# Sheet3.net
KiCad netlist of a schematic drawn in Altium Designer
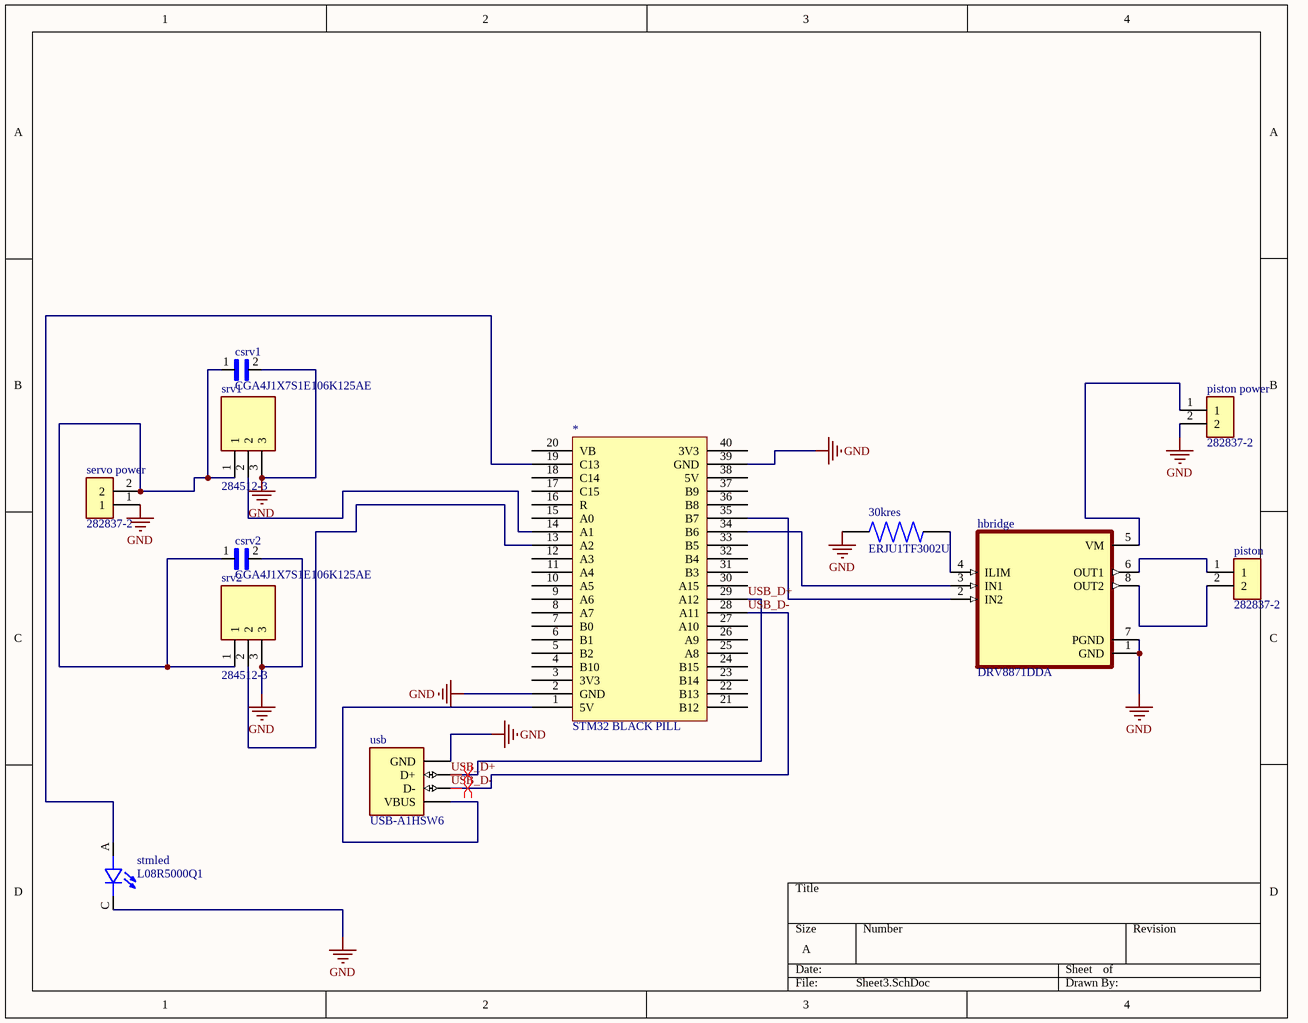
[diagram p0: Sheet3.SchDoc]

(export (version "E")
  (design (tool "Eeschema 10.0.6"))
  (components
    (comp (ref "*")
      (value "STM32 BLACK PILL")
      (footprint "STM 32 Black Pill")
      (fields (field (name "SOURCE") "STM 32 Balck Pill.SchLib"))
      (libsource (lib "Es John") (part "STM32 BLACK PILL"))
    )
    (comp (ref "30kres")
      (value "ERJU1TF3002U")
      (footprint "RES_ERJU1TF3002U")
      (libsource (lib "ERJU1TF3002U") (part "ERJU1TF3002U"))
    )
    (comp (ref "csrv1")
      (value "CGA4J1X7S1E106K125AE")
      (footprint "CAPC2012X150N")
      (description "10 ÂµF Â±10% 25V Ceramic Capacitor X7S 0805 (2012 Metric)")
      (fields (field (name "MF") "TDK") (field (name "DIGI-KEY_PART_NUMBER") "445-181411-2-ND"))
      (libsource (lib "CGA4J1X7S1E106K125AE") (part "CGA4J1X7S1E106K125AE"))
    )
    (comp (ref "csrv2")
      (value "CGA4J1X7S1E106K125AE")
      (footprint "CAPC2012X150N")
      (description "10 ÂµF Â±10% 25V Ceramic Capacitor X7S 0805 (2012 Metric)")
      (fields (field (name "MF") "TDK") (field (name "DIGI-KEY_PART_NUMBER") "445-181411-2-ND"))
      (libsource (lib "CGA4J1X7S1E106K125AE") (part "CGA4J1X7S1E106K125AE"))
    )
    (comp (ref "hbridge")
      (value "DRV8871DDA")
      (footprint "VREG_LM5017MR/NOPB")
      (description "50-V, 3.6-A H-bridge motor driver with integrated current sensing")
      (fields (field (name "MF") "Texas Instruments"))
      (libsource (lib "DRV8871DDA") (part "DRV8871DDA"))
    )
    (comp (ref "piston")
      (value "282837-2")
      (footprint "TE_282837-2")
      (fields (field (name "MF") "TE Connectivity"))
      (libsource (lib "282837-2 (1)") (part "282837-2"))
    )
    (comp (ref "piston power")
      (value "282837-2")
      (footprint "TE_282837-2")
      (fields (field (name "MF") "TE Connectivity"))
      (libsource (lib "282837-2 (1)") (part "282837-2"))
    )
    (comp (ref "servo power")
      (value "282837-2")
      (footprint "TE_282837-2")
      (fields (field (name "MF") "TE Connectivity"))
      (libsource (lib "") (part "282837-2_1"))
    )
    (comp (ref "srv1")
      (value "284512-3")
      (footprint "TE_284512-3")
      (fields (field (name "MF") "TE Connectivity"))
      (libsource (lib "284512-3") (part "284512-3"))
    )
    (comp (ref "srv2")
      (value "284512-3")
      (footprint "TE_284512-3")
      (fields (field (name "MF") "TE Connectivity"))
      (libsource (lib "284512-3") (part "284512-3"))
    )
    (comp (ref "stmled")
      (value "L08R5000Q1")
      (footprint "LEDRD254W57D500H1070")
      (fields (field (name "MF") "LED Technology"))
      (libsource (lib "L08R5000Q1") (part "L08R5000Q1"))
    )
    (comp (ref "usb")
      (value "USB-A1HSW6")
      (footprint "OST_USB-A1HSW6")
      (fields (field (name "MF") "{'manufacturer': u'On Shore Technology Inc.'}"))
      (libsource (lib "USB-A1HSW6") (part "USB-A1HSW6"))
    )
  )
  (nets
    (net (code "1") (name "/USB_D+") (class "Default")
      (node (ref "*") (pin "29") (pinfunction "A12_29") (pintype "passive"))
      (node (ref "usb") (pin "3") (pinfunction "D+_3") (pintype "bidirectional"))
    )
    (net (code "2") (name "/USB_D-") (class "Default")
      (node (ref "*") (pin "28") (pinfunction "A11_28") (pintype "passive"))
      (node (ref "usb") (pin "2") (pinfunction "D-_2") (pintype "bidirectional"))
    )
    (net (code "3") (name "GND") (class "Default")
      (node (ref "*") (pin "2") (pinfunction "GND_2") (pintype "passive"))
      (node (ref "*") (pin "39") (pinfunction "GND_39") (pintype "passive"))
      (node (ref "30kres") (pin "1") (pinfunction "1_1") (pintype "passive"))
      (node (ref "csrv1") (pin "2") (pinfunction "2_2") (pintype "passive"))
      (node (ref "csrv2") (pin "2") (pinfunction "2_2") (pintype "passive"))
      (node (ref "hbridge") (pin "1") (pinfunction "GND_1") (pintype "power_in"))
      (node (ref "hbridge") (pin "7") (pinfunction "PGND_7") (pintype "power_in"))
      (node (ref "piston power") (pin "2") (pinfunction "2_2") (pintype "passive"))
      (node (ref "servo power") (pin "1") (pinfunction "1_1") (pintype "passive"))
      (node (ref "srv1") (pin "3") (pinfunction "3_3") (pintype "passive"))
      (node (ref "srv2") (pin "3") (pinfunction "3_3") (pintype "passive"))
      (node (ref "stmled") (pin "C") (pinfunction "C_C") (pintype "passive"))
      (node (ref "usb") (pin "4") (pinfunction "GND_4") (pintype "power_in"))
    )
    (net (code "4") (name "Net-(*-A1)") (class "Default")
      (node (ref "*") (pin "14") (pinfunction "A1_14") (pintype "passive"))
      (node (ref "srv1") (pin "2") (pinfunction "2_2") (pintype "passive"))
    )
    (net (code "5") (name "Net-(*-A2)") (class "Default")
      (node (ref "*") (pin "13") (pinfunction "A2_13") (pintype "passive"))
      (node (ref "srv2") (pin "2") (pinfunction "2_2") (pintype "passive"))
    )
    (net (code "6") (name "Net-(*-B6)") (class "Default")
      (node (ref "*") (pin "34") (pinfunction "B6_34") (pintype "passive"))
      (node (ref "hbridge") (pin "3") (pinfunction "IN1_3") (pintype "input"))
    )
    (net (code "7") (name "Net-(*-B7)") (class "Default")
      (node (ref "*") (pin "35") (pinfunction "B7_35") (pintype "passive"))
      (node (ref "hbridge") (pin "2") (pinfunction "IN2_2") (pintype "input"))
    )
    (net (code "8") (name "Net-(*-C13)") (class "Default")
      (node (ref "*") (pin "19") (pinfunction "C13_19") (pintype "passive"))
      (node (ref "stmled") (pin "A") (pinfunction "A_A") (pintype "passive"))
    )
    (net (code "9") (name "Net-(csrv1-Pad1)") (class "Default")
      (node (ref "csrv1") (pin "1") (pinfunction "1_1") (pintype "passive"))
      (node (ref "csrv2") (pin "1") (pinfunction "1_1") (pintype "passive"))
      (node (ref "servo power") (pin "2") (pinfunction "2_2") (pintype "passive"))
      (node (ref "srv1") (pin "1") (pinfunction "1_1") (pintype "passive"))
      (node (ref "srv2") (pin "1") (pinfunction "1_1") (pintype "passive"))
    )
    (net (code "10") (name "Net-(hbridge-ILIM)") (class "Default")
      (node (ref "30kres") (pin "2") (pinfunction "2_2") (pintype "passive"))
      (node (ref "hbridge") (pin "4") (pinfunction "ILIM_4") (pintype "input"))
    )
    (net (code "11") (name "Net-(hbridge-OUT1)") (class "Default")
      (node (ref "hbridge") (pin "6") (pinfunction "OUT1_6") (pintype "output"))
      (node (ref "piston") (pin "1") (pinfunction "1_1") (pintype "passive"))
    )
    (net (code "12") (name "Net-(hbridge-OUT2)") (class "Default")
      (node (ref "hbridge") (pin "8") (pinfunction "OUT2_8") (pintype "output"))
      (node (ref "piston") (pin "2") (pinfunction "2_2") (pintype "passive"))
    )
    (net (code "13") (name "Net-(hbridge-VM)") (class "Default")
      (node (ref "hbridge") (pin "5") (pinfunction "VM_5") (pintype "power_in"))
      (node (ref "piston power") (pin "1") (pinfunction "1_1") (pintype "passive"))
    )
    (net (code "14") (name "Net-(usb-VBUS)") (class "Default")
      (node (ref "*") (pin "1") (pinfunction "5V_1") (pintype "passive"))
      (node (ref "usb") (pin "1") (pinfunction "VBUS_1") (pintype "power_in"))
    )
    (net (code "15") (name "unconnected-(*-3V3-Pad3)") (class "Default")
      (node (ref "*") (pin "3") (pinfunction "3V3_3") (pintype "passive"))
    )
    (net (code "16") (name "unconnected-(*-3V3-Pad40)") (class "Default")
      (node (ref "*") (pin "40") (pinfunction "3V3_40") (pintype "passive"))
    )
    (net (code "17") (name "unconnected-(*-5V-Pad38)") (class "Default")
      (node (ref "*") (pin "38") (pinfunction "5V_38") (pintype "passive"))
    )
    (net (code "18") (name "unconnected-(*-A0-Pad15)") (class "Default")
      (node (ref "*") (pin "15") (pinfunction "A0_15") (pintype "passive"))
    )
    (net (code "19") (name "unconnected-(*-A3-Pad12)") (class "Default")
      (node (ref "*") (pin "12") (pinfunction "A3_12") (pintype "passive"))
    )
    (net (code "20") (name "unconnected-(*-A4-Pad11)") (class "Default")
      (node (ref "*") (pin "11") (pinfunction "A4_11") (pintype "passive"))
    )
    (net (code "21") (name "unconnected-(*-A5-Pad10)") (class "Default")
      (node (ref "*") (pin "10") (pinfunction "A5_10") (pintype "passive"))
    )
    (net (code "22") (name "unconnected-(*-A6-Pad9)") (class "Default")
      (node (ref "*") (pin "9") (pinfunction "A6_9") (pintype "passive"))
    )
    (net (code "23") (name "unconnected-(*-A7-Pad8)") (class "Default")
      (node (ref "*") (pin "8") (pinfunction "A7_8") (pintype "passive"))
    )
    (net (code "24") (name "unconnected-(*-A8-Pad25)") (class "Default")
      (node (ref "*") (pin "25") (pinfunction "A8_25") (pintype "passive"))
    )
    (net (code "25") (name "unconnected-(*-A9-Pad26)") (class "Default")
      (node (ref "*") (pin "26") (pinfunction "A9_26") (pintype "passive"))
    )
    (net (code "26") (name "unconnected-(*-A10-Pad27)") (class "Default")
      (node (ref "*") (pin "27") (pinfunction "A10_27") (pintype "passive"))
    )
    (net (code "27") (name "unconnected-(*-A15-Pad30)") (class "Default")
      (node (ref "*") (pin "30") (pinfunction "A15_30") (pintype "passive"))
    )
    (net (code "28") (name "unconnected-(*-B0-Pad7)") (class "Default")
      (node (ref "*") (pin "7") (pinfunction "B0_7") (pintype "passive"))
    )
    (net (code "29") (name "unconnected-(*-B1-Pad6)") (class "Default")
      (node (ref "*") (pin "6") (pinfunction "B1_6") (pintype "passive"))
    )
    (net (code "30") (name "unconnected-(*-B2-Pad5)") (class "Default")
      (node (ref "*") (pin "5") (pinfunction "B2_5") (pintype "passive"))
    )
    (net (code "31") (name "unconnected-(*-B3-Pad31)") (class "Default")
      (node (ref "*") (pin "31") (pinfunction "B3_31") (pintype "passive"))
    )
    (net (code "32") (name "unconnected-(*-B4-Pad32)") (class "Default")
      (node (ref "*") (pin "32") (pinfunction "B4_32") (pintype "passive"))
    )
    (net (code "33") (name "unconnected-(*-B5-Pad33)") (class "Default")
      (node (ref "*") (pin "33") (pinfunction "B5_33") (pintype "passive"))
    )
    (net (code "34") (name "unconnected-(*-B8-Pad36)") (class "Default")
      (node (ref "*") (pin "36") (pinfunction "B8_36") (pintype "passive"))
    )
    (net (code "35") (name "unconnected-(*-B9-Pad37)") (class "Default")
      (node (ref "*") (pin "37") (pinfunction "B9_37") (pintype "passive"))
    )
    (net (code "36") (name "unconnected-(*-B10-Pad4)") (class "Default")
      (node (ref "*") (pin "4") (pinfunction "B10_4") (pintype "passive"))
    )
    (net (code "37") (name "unconnected-(*-B12-Pad21)") (class "Default")
      (node (ref "*") (pin "21") (pinfunction "B12_21") (pintype "passive"))
    )
    (net (code "38") (name "unconnected-(*-B13-Pad22)") (class "Default")
      (node (ref "*") (pin "22") (pinfunction "B13_22") (pintype "passive"))
    )
    (net (code "39") (name "unconnected-(*-B14-Pad23)") (class "Default")
      (node (ref "*") (pin "23") (pinfunction "B14_23") (pintype "passive"))
    )
    (net (code "40") (name "unconnected-(*-B15-Pad24)") (class "Default")
      (node (ref "*") (pin "24") (pinfunction "B15_24") (pintype "passive"))
    )
    (net (code "41") (name "unconnected-(*-C14-Pad18)") (class "Default")
      (node (ref "*") (pin "18") (pinfunction "C14_18") (pintype "passive"))
    )
    (net (code "42") (name "unconnected-(*-C15-Pad17)") (class "Default")
      (node (ref "*") (pin "17") (pinfunction "C15_17") (pintype "passive"))
    )
    (net (code "43") (name "unconnected-(*-R-Pad16)") (class "Default")
      (node (ref "*") (pin "16") (pinfunction "R_16") (pintype "passive"))
    )
    (net (code "44") (name "unconnected-(*-VB-Pad20)") (class "Default")
      (node (ref "*") (pin "20") (pinfunction "VB_20") (pintype "passive"))
    )
  )
)
